# NG2094_LEFT_OV9282.net
KiCad netlist of a schematic drawn in Altium Designer
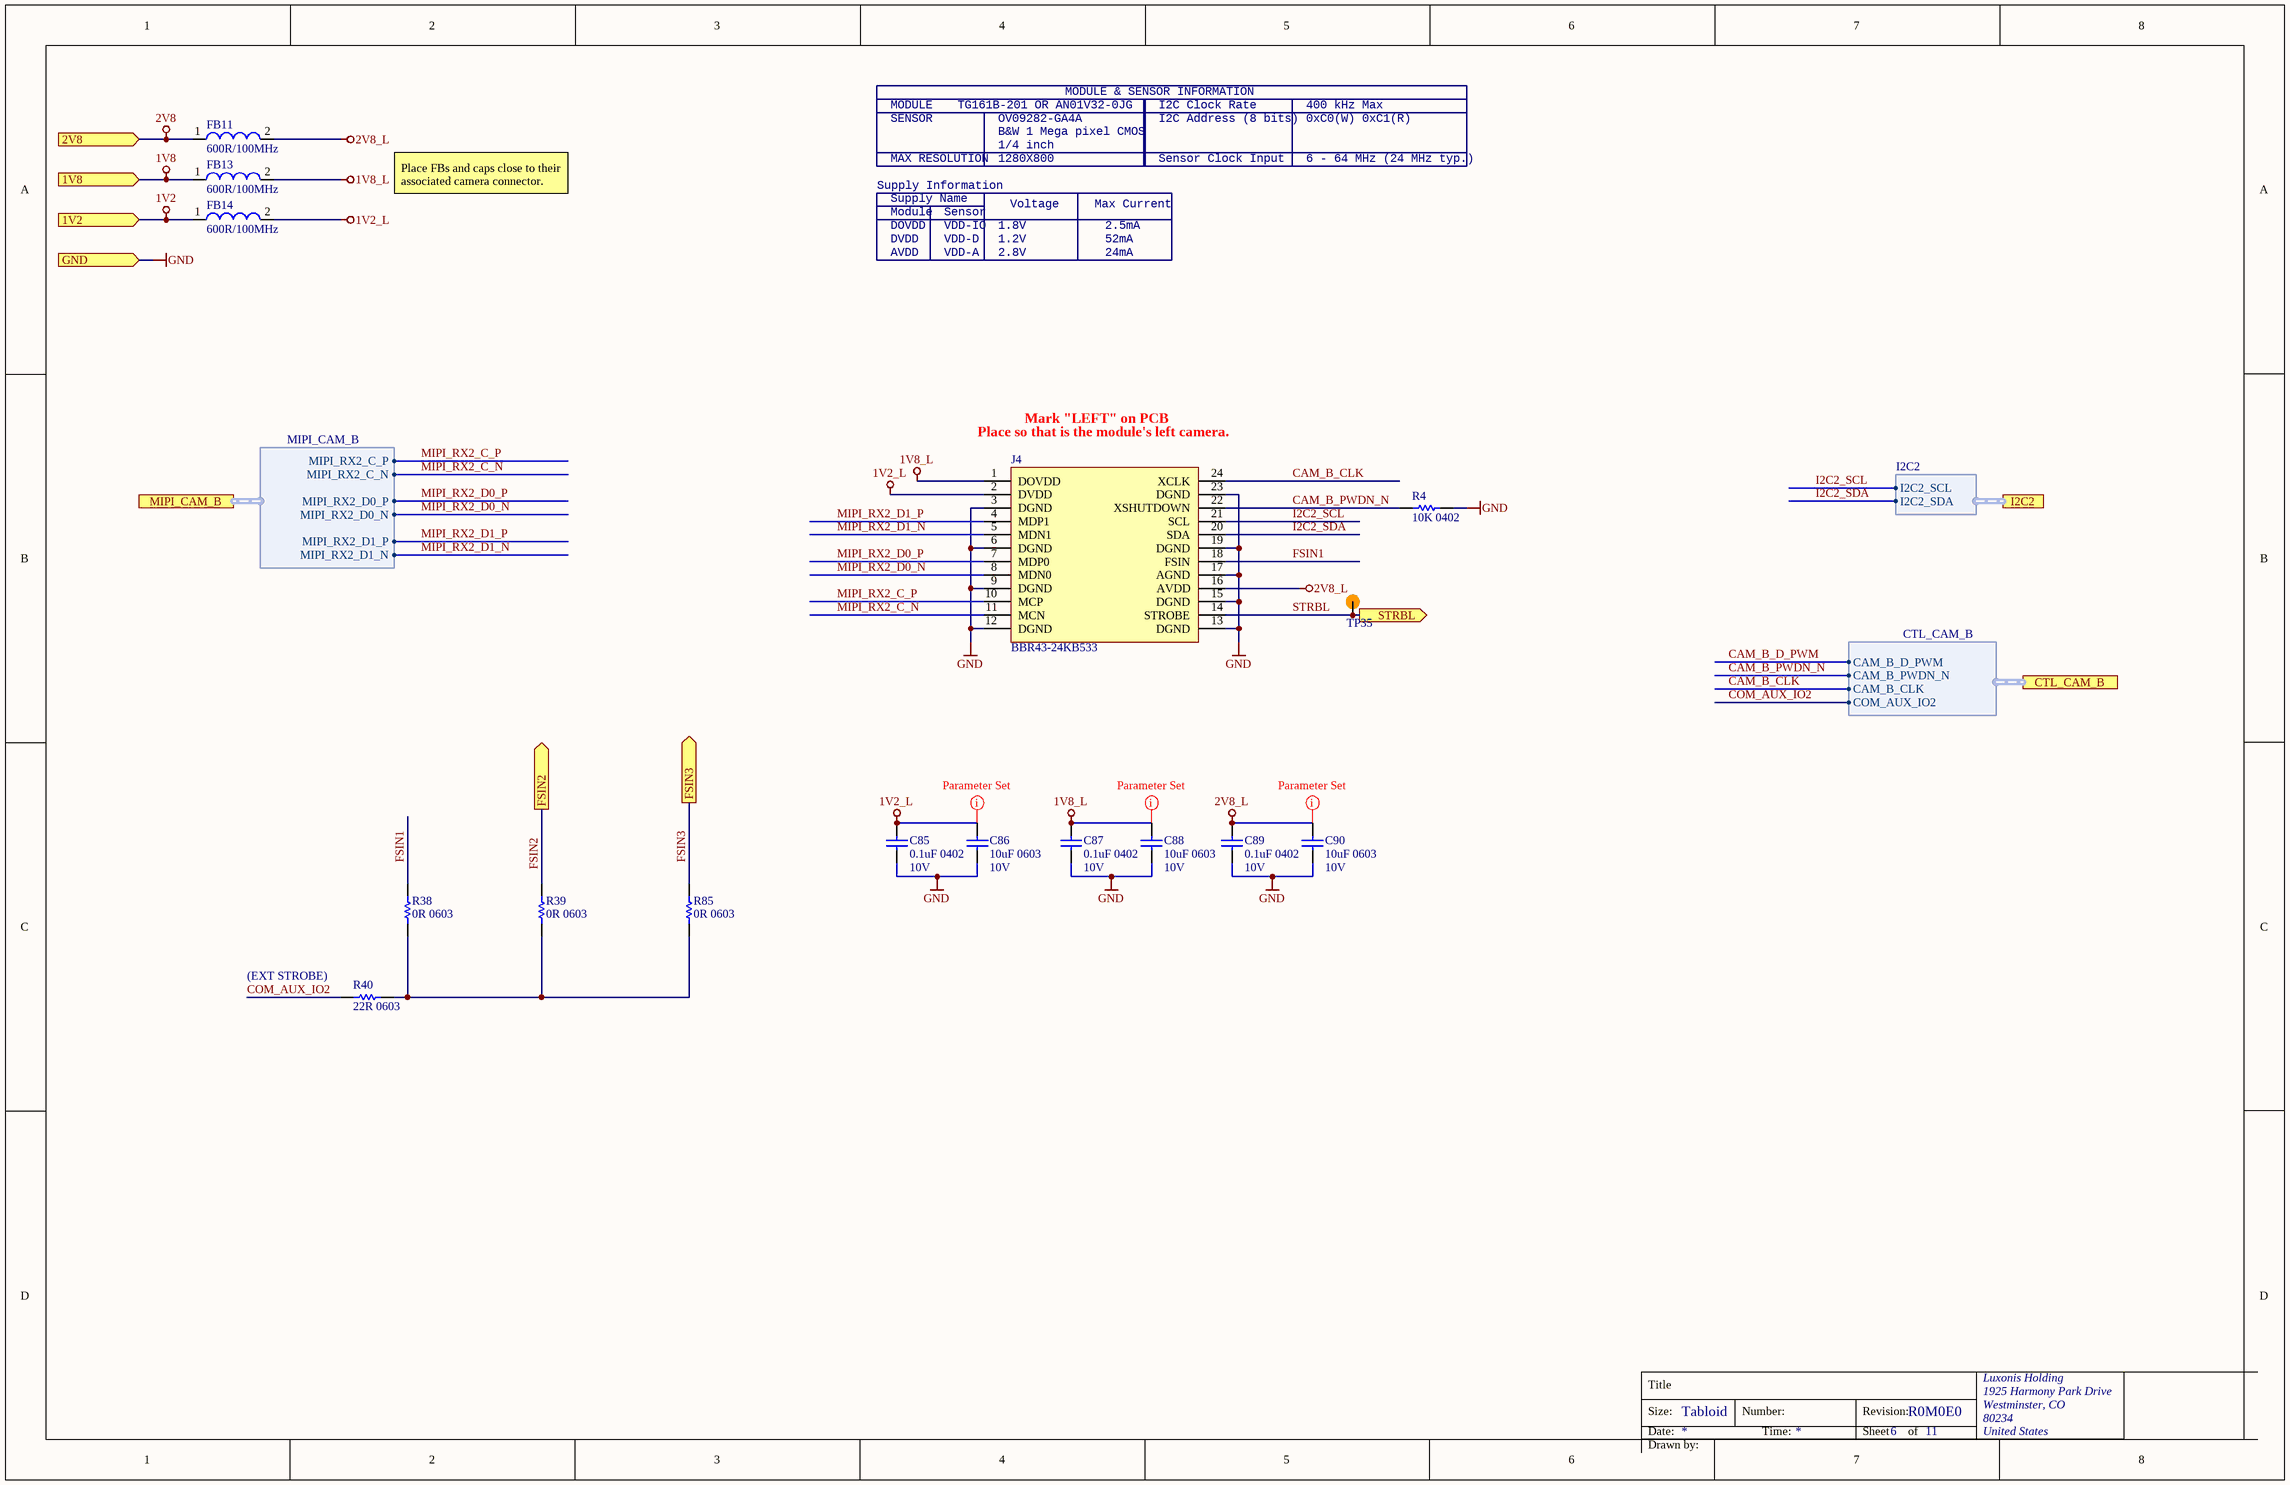
[diagram p0: NG2094_LEFT_OV9282.SchDoc]

(export (version "E")
  (design (tool "Eeschema 10.0.6"))
  (components
    (comp (ref "C85")
      (value "0.1uF 0402")
      (footprint "CAP_Altium_Vault_Generic:CAPC0402(1005)70_L")
      (description "CAP CER 0.1UF 10V X7R 0402 5%")
      (fields (field (name "TOLERANCE") "5%") (field (name "VOLTAGE RATING") "10V"))
      (libsource (lib "LuxonisMaster") (part "GRM155R71A104JA01D"))
    )
    (comp (ref "C86")
      (value "10uF 0603")
      (footprint "CAP_Altium_Vault_Generic:CAPC0603(1608)100_L")
      (description "CAP CER 10UF 10V X5R 0603 20%")
      (fields (field (name "TOLERANCE") "20%") (field (name "VOLTAGE RATING") "10V"))
      (libsource (lib "LuxonisMaster") (part "GRM188R61A106ME69D"))
    )
    (comp (ref "C87")
      (value "0.1uF 0402")
      (footprint "CAP_Altium_Vault_Generic:CAPC0402(1005)70_L")
      (description "CAP CER 0.1UF 10V X7R 0402 5%")
      (fields (field (name "TOLERANCE") "5%") (field (name "VOLTAGE RATING") "10V"))
      (libsource (lib "LuxonisMaster") (part "GRM155R71A104JA01D"))
    )
    (comp (ref "C88")
      (value "10uF 0603")
      (footprint "CAP_Altium_Vault_Generic:CAPC0603(1608)100_L")
      (description "CAP CER 10UF 10V X5R 0603 20%")
      (fields (field (name "TOLERANCE") "20%") (field (name "VOLTAGE RATING") "10V"))
      (libsource (lib "LuxonisMaster") (part "GRM188R61A106ME69D"))
    )
    (comp (ref "C89")
      (value "0.1uF 0402")
      (footprint "CAP_Altium_Vault_Generic:CAPC0402(1005)70_L")
      (description "CAP CER 0.1UF 10V X7R 0402 5%")
      (fields (field (name "TOLERANCE") "5%") (field (name "VOLTAGE RATING") "10V"))
      (libsource (lib "LuxonisMaster") (part "GRM155R71A104JA01D"))
    )
    (comp (ref "C90")
      (value "10uF 0603")
      (footprint "CAP_Altium_Vault_Generic:CAPC0603(1608)100_L")
      (description "CAP CER 10UF 10V X5R 0603 20%")
      (fields (field (name "TOLERANCE") "20%") (field (name "VOLTAGE RATING") "10V"))
      (libsource (lib "LuxonisMaster") (part "GRM188R61A106ME69D"))
    )
    (comp (ref "FB11")
      (value "600R/100MHz")
      (footprint "LuxonisMaster:2508056017Y2")
      (description "FERRITE BEAD, 0.1OHM, 2A, 0805, 600R/100MHz")
      (fields (field (name "TOLERANCE") "25%"))
      (libsource (lib "LuxonisMaster") (part "2508056017Y2"))
    )
    (comp (ref "FB13")
      (value "600R/100MHz")
      (footprint "LuxonisMaster:2508056017Y2")
      (description "FERRITE BEAD, 0.1OHM, 2A, 0805, 600R/100MHz")
      (fields (field (name "TOLERANCE") "25%"))
      (libsource (lib "LuxonisMaster") (part "2508056017Y2"))
    )
    (comp (ref "FB14")
      (value "600R/100MHz")
      (footprint "LuxonisMaster:2508056017Y2")
      (description "FERRITE BEAD, 0.1OHM, 2A, 0805, 600R/100MHz")
      (fields (field (name "TOLERANCE") "25%"))
      (libsource (lib "LuxonisMaster") (part "2508056017Y2"))
    )
    (comp (ref "J4")
      (value "BBR43-24KB533")
      (footprint "TG161B-201_W")
      (description "CONN 24 way, 2 row board to board connector SMD")
      (libsource (lib "LuxonisMaster") (part "TG161B-201_Connector"))
    )
    (comp (ref "R4")
      (value "10K 0402")
      (footprint "RES_Altium_Vault_Generic:RESC0402(1005)_L")
      (fields (field (name "TOLERANCE") "1%"))
      (libsource (lib "LuxonisMaster") (part "RC0402FR-1310KL"))
    )
    (comp (ref "R38")
      (value "0R 0603")
      (footprint "RES_Altium_Vault_Generic:RESC0603(1608)_L")
      (fields (field (name "TOLERANCE") "5%"))
      (libsource (lib "LuxonisMaster") (part "CRCW06030000Z0EA"))
    )
    (comp (ref "R39")
      (value "0R 0603")
      (footprint "RES_Altium_Vault_Generic:RESC0603(1608)_L")
      (fields (field (name "TOLERANCE") "5%"))
      (libsource (lib "LuxonisMaster") (part "CRCW06030000Z0EA"))
    )
    (comp (ref "R40")
      (value "22R 0603")
      (footprint "RESC0603(1608)_L")
      (description "RES SMD 22 OHM 1% 1/10W 0603")
      (fields (field (name "TOLERANCE") "1%"))
      (libsource (lib "LuxonisMaster") (part "RC0603FR-0722RL"))
    )
    (comp (ref "R85")
      (value "0R 0603")
      (footprint "RES_Altium_Vault_Generic:RESC0603(1608)_L")
      (fields (field (name "TOLERANCE") "5%"))
      (libsource (lib "LuxonisMaster") (part "CRCW06030000Z0EA"))
    )
    (comp (ref "TP35")
      (value "TP100_200_NS")
      (footprint "LuxonisMaster:TP100_200_NS")
      (libsource (lib "LuxonisMaster") (part "TEST_POINT"))
    )
  )
  (nets
    (net (code "4") (name "/CAM_B_CLK") (class "Default")
      (node (ref "J4") (pin "24") (pinfunction "XCLK_24") (pintype "passive"))
    )
    (net (code "6") (name "/CAM_B_PWDN_N") (class "Default")
      (node (ref "J4") (pin "22") (pinfunction "XSHUTDOWN_22") (pintype "passive"))
      (node (ref "R4") (pin "1") (pinfunction "1_1") (pintype "passive"))
    )
    (net (code "7") (name "/COM_AUX_IO2") (class "Default")
      (node (ref "R40") (pin "2") (pinfunction "2_2") (pintype "passive"))
    )
    (net (code "8") (name "/FSIN1") (class "Default")
      (node (ref "J4") (pin "18") (pinfunction "FSIN_18") (pintype "passive"))
      (node (ref "R38") (pin "2") (pinfunction "2_2") (pintype "passive"))
    )
    (net (code "9") (name "/FSIN2") (class "Default")
      (node (ref "R39") (pin "2") (pinfunction "2_2") (pintype "passive"))
    )
    (net (code "10") (name "/FSIN3") (class "Default")
      (node (ref "R85") (pin "2") (pinfunction "2_2") (pintype "passive"))
    )
    (net (code "11") (name "/I2C2_SCL") (class "Default")
      (node (ref "J4") (pin "21") (pinfunction "SCL_21") (pintype "passive"))
    )
    (net (code "12") (name "/I2C2_SDA") (class "Default")
      (node (ref "J4") (pin "20") (pinfunction "SDA_20") (pintype "passive"))
    )
    (net (code "13") (name "/MIPI_RX2_C_N") (class "Default")
      (node (ref "J4") (pin "11") (pinfunction "MCN_11") (pintype "passive"))
    )
    (net (code "14") (name "/MIPI_RX2_C_P") (class "Default")
      (node (ref "J4") (pin "10") (pinfunction "MCP_10") (pintype "passive"))
    )
    (net (code "15") (name "/MIPI_RX2_D0_N") (class "Default")
      (node (ref "J4") (pin "8") (pinfunction "MDN0_8") (pintype "passive"))
    )
    (net (code "16") (name "/MIPI_RX2_D0_P") (class "Default")
      (node (ref "J4") (pin "7") (pinfunction "MDP0_7") (pintype "passive"))
    )
    (net (code "17") (name "/MIPI_RX2_D1_N") (class "Default")
      (node (ref "J4") (pin "5") (pinfunction "MDN1_5") (pintype "passive"))
    )
    (net (code "18") (name "/MIPI_RX2_D1_P") (class "Default")
      (node (ref "J4") (pin "4") (pinfunction "MDP1_4") (pintype "passive"))
    )
    (net (code "19") (name "/STRBL") (class "Default")
      (node (ref "J4") (pin "14") (pinfunction "STROBE_14") (pintype "passive"))
      (node (ref "TP35") (pin "1") (pintype "passive"))
    )
    (net (code "23") (name "1V2") (class "Default")
      (node (ref "FB14") (pin "1") (pinfunction "1_1") (pintype "passive"))
    )
    (net (code "24") (name "1V2_L") (class "Default")
      (node (ref "C85") (pin "2") (pinfunction "2_2") (pintype "passive"))
      (node (ref "C86") (pin "2") (pinfunction "2_2") (pintype "passive"))
      (node (ref "FB14") (pin "2") (pinfunction "2_2") (pintype "passive"))
      (node (ref "J4") (pin "2") (pinfunction "DVDD_2") (pintype "passive"))
    )
    (net (code "25") (name "1V8") (class "Default")
      (node (ref "FB13") (pin "1") (pinfunction "1_1") (pintype "passive"))
    )
    (net (code "26") (name "1V8_L") (class "Default")
      (node (ref "C87") (pin "2") (pinfunction "2_2") (pintype "passive"))
      (node (ref "C88") (pin "2") (pinfunction "2_2") (pintype "passive"))
      (node (ref "FB13") (pin "2") (pinfunction "2_2") (pintype "passive"))
      (node (ref "J4") (pin "1") (pinfunction "DOVDD_1") (pintype "passive"))
    )
    (net (code "27") (name "2V8") (class "Default")
      (node (ref "FB11") (pin "1") (pinfunction "1_1") (pintype "passive"))
    )
    (net (code "28") (name "2V8_L") (class "Default")
      (node (ref "C89") (pin "2") (pinfunction "2_2") (pintype "passive"))
      (node (ref "C90") (pin "2") (pinfunction "2_2") (pintype "passive"))
      (node (ref "FB11") (pin "2") (pinfunction "2_2") (pintype "passive"))
      (node (ref "J4") (pin "16") (pinfunction "AVDD_16") (pintype "passive"))
    )
    (net (code "29") (name "GND") (class "Default")
      (node (ref "C85") (pin "1") (pinfunction "1_1") (pintype "passive"))
      (node (ref "C86") (pin "1") (pinfunction "1_1") (pintype "passive"))
      (node (ref "C87") (pin "1") (pinfunction "1_1") (pintype "passive"))
      (node (ref "C88") (pin "1") (pinfunction "1_1") (pintype "passive"))
      (node (ref "C89") (pin "1") (pinfunction "1_1") (pintype "passive"))
      (node (ref "C90") (pin "1") (pinfunction "1_1") (pintype "passive"))
      (node (ref "J4") (pin "12") (pinfunction "DGND_12") (pintype "passive"))
      (node (ref "J4") (pin "13") (pinfunction "DGND_13") (pintype "passive"))
      (node (ref "J4") (pin "15") (pinfunction "DGND_15") (pintype "passive"))
      (node (ref "J4") (pin "17") (pinfunction "AGND_17") (pintype "passive"))
      (node (ref "J4") (pin "19") (pinfunction "DGND_19") (pintype "passive"))
      (node (ref "J4") (pin "23") (pinfunction "DGND_23") (pintype "passive"))
      (node (ref "J4") (pin "3") (pinfunction "DGND_3") (pintype "passive"))
      (node (ref "J4") (pin "6") (pinfunction "DGND_6") (pintype "passive"))
      (node (ref "J4") (pin "9") (pinfunction "DGND_9") (pintype "passive"))
      (node (ref "R4") (pin "2") (pinfunction "2_2") (pintype "passive"))
    )
    (net (code "30") (name "Net-(R38-Pad1)") (class "Default")
      (node (ref "R38") (pin "1") (pinfunction "1_1") (pintype "passive"))
      (node (ref "R39") (pin "1") (pinfunction "1_1") (pintype "passive"))
      (node (ref "R40") (pin "1") (pinfunction "1_1") (pintype "passive"))
      (node (ref "R85") (pin "1") (pinfunction "1_1") (pintype "passive"))
    )
  )
)
